# STLink_MODS.net
KiCad netlist of a schematic drawn in Altium Designer
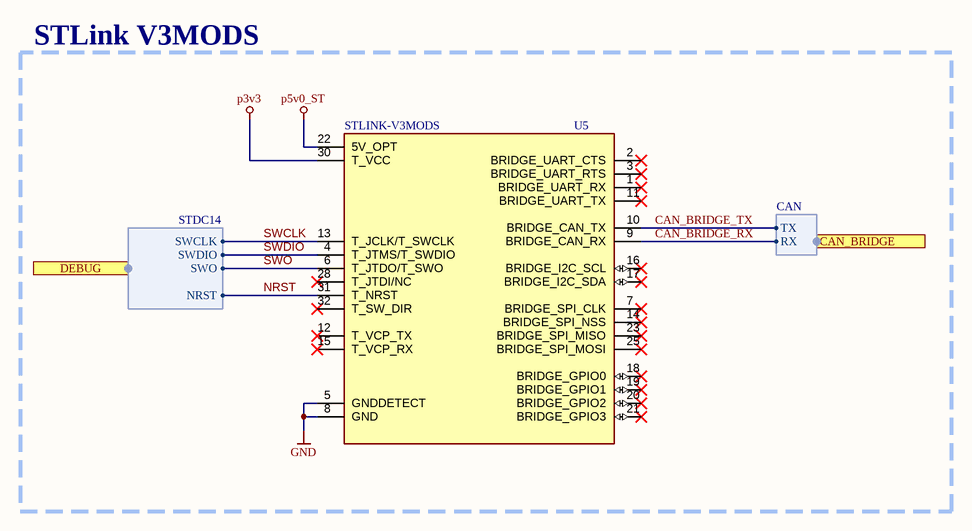
[diagram p0: STLink_MODS.SchDoc]

(export (version "E")
  (design (tool "Eeschema 10.0.6"))
  (components
    (comp (ref "U5")
      (value "STLINK-V3MODS")
      (footprint "MODULE_STLINK-V3MODS")
      (libsource (lib "Green Team Twente") (part "STLINK-V3MODS"))
    )
  )
  (nets
    (net (code "3") (name "/CAN_BRIDGE_RX") (class "Default")
      (node (ref "U5") (pin "9") (pinfunction "BRIDGE_CAN_RX_9") (pintype "passive"))
    )
    (net (code "4") (name "/CAN_BRIDGE_TX") (class "Default")
      (node (ref "U5") (pin "10") (pinfunction "BRIDGE_CAN_TX_10") (pintype "passive"))
    )
    (net (code "5") (name "/NRST") (class "Default")
      (node (ref "U5") (pin "31") (pinfunction "T_NRST_31") (pintype "passive"))
    )
    (net (code "6") (name "/SWCLK") (class "Default")
      (node (ref "U5") (pin "13") (pinfunction "T_JCLK/T_SWCLK_13") (pintype "passive"))
    )
    (net (code "7") (name "/SWDIO") (class "Default")
      (node (ref "U5") (pin "4") (pinfunction "T_JTMS/T_SWDIO_4") (pintype "passive"))
    )
    (net (code "8") (name "/SWO") (class "Default")
      (node (ref "U5") (pin "6") (pinfunction "T_JTDO/T_SWO_6") (pintype "passive"))
    )
    (net (code "11") (name "GND") (class "Default")
      (node (ref "U5") (pin "5") (pinfunction "GNDDETECT_5") (pintype "power_in"))
      (node (ref "U5") (pin "8") (pinfunction "GND_8") (pintype "power_in"))
    )
    (net (code "12") (name "p3v3") (class "Default")
      (node (ref "U5") (pin "30") (pinfunction "T_VCC_30") (pintype "passive"))
    )
    (net (code "13") (name "p5v0_ST") (class "Default")
      (node (ref "U5") (pin "22") (pinfunction "5V_OPT_22") (pintype "passive"))
    )
    (net (code "14") (name "unconnected-(U5-BRIDGE_GPIO0-Pad18)") (class "Default")
      (node (ref "U5") (pin "18") (pinfunction "BRIDGE_GPIO0_18") (pintype "bidirectional+no_connect"))
    )
    (net (code "15") (name "unconnected-(U5-BRIDGE_GPIO1-Pad19)") (class "Default")
      (node (ref "U5") (pin "19") (pinfunction "BRIDGE_GPIO1_19") (pintype "bidirectional+no_connect"))
    )
    (net (code "16") (name "unconnected-(U5-BRIDGE_GPIO2-Pad20)") (class "Default")
      (node (ref "U5") (pin "20") (pinfunction "BRIDGE_GPIO2_20") (pintype "bidirectional+no_connect"))
    )
    (net (code "17") (name "unconnected-(U5-BRIDGE_GPIO3-Pad21)") (class "Default")
      (node (ref "U5") (pin "21") (pinfunction "BRIDGE_GPIO3_21") (pintype "bidirectional+no_connect"))
    )
    (net (code "18") (name "unconnected-(U5-BRIDGE_I2C_SCL-Pad16)") (class "Default")
      (node (ref "U5") (pin "16") (pinfunction "BRIDGE_I2C_SCL_16") (pintype "bidirectional+no_connect"))
    )
    (net (code "19") (name "unconnected-(U5-BRIDGE_I2C_SDA-Pad17)") (class "Default")
      (node (ref "U5") (pin "17") (pinfunction "BRIDGE_I2C_SDA_17") (pintype "bidirectional+no_connect"))
    )
    (net (code "20") (name "unconnected-(U5-BRIDGE_SPI_CLK-Pad7)") (class "Default")
      (node (ref "U5") (pin "7") (pinfunction "BRIDGE_SPI_CLK_7") (pintype "passive+no_connect"))
    )
    (net (code "21") (name "unconnected-(U5-BRIDGE_SPI_MISO-Pad23)") (class "Default")
      (node (ref "U5") (pin "23") (pinfunction "BRIDGE_SPI_MISO_23") (pintype "passive+no_connect"))
    )
    (net (code "22") (name "unconnected-(U5-BRIDGE_SPI_MOSI-Pad25)") (class "Default")
      (node (ref "U5") (pin "25") (pinfunction "BRIDGE_SPI_MOSI_25") (pintype "passive+no_connect"))
    )
    (net (code "23") (name "unconnected-(U5-BRIDGE_SPI_NSS-Pad14)") (class "Default")
      (node (ref "U5") (pin "14") (pinfunction "BRIDGE_SPI_NSS_14") (pintype "passive+no_connect"))
    )
    (net (code "24") (name "unconnected-(U5-BRIDGE_UART_CTS-Pad2)") (class "Default")
      (node (ref "U5") (pin "2") (pinfunction "BRIDGE_UART_CTS_2") (pintype "passive+no_connect"))
    )
    (net (code "25") (name "unconnected-(U5-BRIDGE_UART_RTS-Pad3)") (class "Default")
      (node (ref "U5") (pin "3") (pinfunction "BRIDGE_UART_RTS_3") (pintype "passive+no_connect"))
    )
    (net (code "26") (name "unconnected-(U5-BRIDGE_UART_RX-Pad1)") (class "Default")
      (node (ref "U5") (pin "1") (pinfunction "BRIDGE_UART_RX_1") (pintype "passive+no_connect"))
    )
    (net (code "27") (name "unconnected-(U5-BRIDGE_UART_TX-Pad11)") (class "Default")
      (node (ref "U5") (pin "11") (pinfunction "BRIDGE_UART_TX_11") (pintype "passive+no_connect"))
    )
    (net (code "28") (name "unconnected-(U5-T_JTDI{slash}NC-Pad28)") (class "Default")
      (node (ref "U5") (pin "28") (pinfunction "T_JTDI/NC_28") (pintype "passive+no_connect"))
    )
    (net (code "29") (name "unconnected-(U5-T_SW_DIR-Pad32)") (class "Default")
      (node (ref "U5") (pin "32") (pinfunction "T_SW_DIR_32") (pintype "passive+no_connect"))
    )
    (net (code "30") (name "unconnected-(U5-T_VCP_RX-Pad15)") (class "Default")
      (node (ref "U5") (pin "15") (pinfunction "T_VCP_RX_15") (pintype "passive+no_connect"))
    )
    (net (code "31") (name "unconnected-(U5-T_VCP_TX-Pad12)") (class "Default")
      (node (ref "U5") (pin "12") (pinfunction "T_VCP_TX_12") (pintype "passive+no_connect"))
    )
  )
)
